# schema_esp01-chata.net
KiCad netlist of a schematic drawn in EAGLE
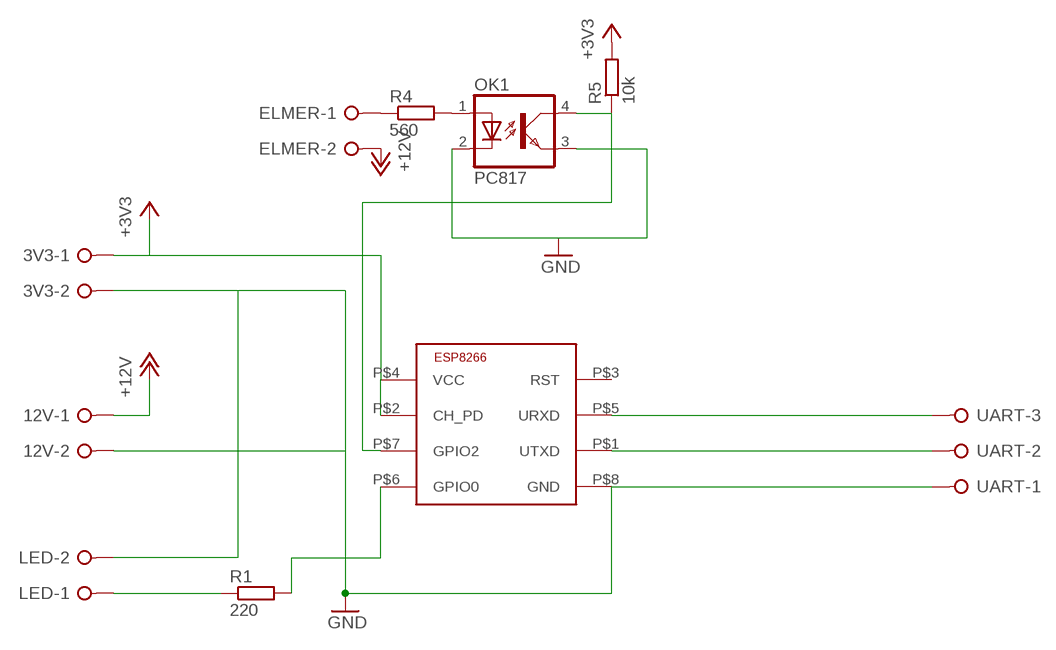
[diagram p0: schematic, sheet 1]

(export (version "E")
  (design (tool "Eeschema 10.0.6"))
  (components
    (comp (ref "3V3")
      (value "W237-02P")
      (footprint "eagle-import:W237-132")
      (libsource (lib "eagle-import") (part "W237-02P"))
    )
    (comp (ref "12V")
      (value "W237-02P")
      (footprint "eagle-import:W237-132")
      (libsource (lib "eagle-import") (part "W237-02P"))
    )
    (comp (ref "ELMER")
      (value "W237-02P")
      (footprint "eagle-import:W237-132")
      (libsource (lib "eagle-import") (part "W237-02P"))
    )
    (comp (ref "LED")
      (value "W237-02P")
      (footprint "eagle-import:W237-132")
      (libsource (lib "eagle-import") (part "W237-02P"))
    )
    (comp (ref "OK1")
      (value "PC817")
      (footprint "eagle-import:DIL04")
      (fields (field (name "MPN") "PC817X4J000F"))
      (libsource (lib "eagle-import") (part "PC817"))
    )
    (comp (ref "R1")
      (value "220")
      (footprint "eagle-import:0204_7")
      (libsource (lib "eagle-import") (part "R-EU_0204/7"))
    )
    (comp (ref "R4")
      (value "560")
      (footprint "eagle-import:0204_7")
      (libsource (lib "eagle-import") (part "R-EU_0204/7"))
    )
    (comp (ref "R5")
      (value "10k")
      (footprint "eagle-import:0204_7")
      (libsource (lib "eagle-import") (part "R-EU_0204/7"))
    )
    (comp (ref "U$1")
      (value "ESP8266-01")
      (footprint "eagle-import:ESP-01")
      (libsource (lib "eagle-import") (part "ESP8266-01"))
    )
    (comp (ref "UART")
      (value "W237-3E")
      (footprint "eagle-import:W237-3E")
      (libsource (lib "eagle-import") (part "W237-3E"))
    )
  )
  (nets
    (net (code "1") (name "+3V3") (class "Default")
      (node (ref "3V3") (pin "1") (pinfunction "KL_1") (pintype "passive"))
      (node (ref "R5") (pin "2") (pinfunction "2_2") (pintype "passive"))
      (node (ref "U$1") (pin "P$2") (pinfunction "CH_PD_P$2") (pintype "bidirectional"))
      (node (ref "U$1") (pin "P$4") (pinfunction "VCC_P$4") (pintype "bidirectional"))
    )
    (net (code "2") (name "+12V") (class "Default")
      (node (ref "12V") (pin "1") (pinfunction "KL_1") (pintype "passive"))
      (node (ref "ELMER") (pin "2") (pinfunction "KL_2") (pintype "passive"))
    )
    (net (code "3") (name "GND") (class "Default")
      (node (ref "12V") (pin "2") (pinfunction "KL_2") (pintype "passive"))
      (node (ref "3V3") (pin "2") (pinfunction "KL_2") (pintype "passive"))
      (node (ref "LED") (pin "2") (pinfunction "KL_2") (pintype "passive"))
      (node (ref "OK1") (pin "2") (pinfunction "C_2") (pintype "passive"))
      (node (ref "OK1") (pin "3") (pinfunction "EMIT_3") (pintype "passive"))
      (node (ref "U$1") (pin "P$8") (pinfunction "GND_P$8") (pintype "bidirectional"))
      (node (ref "UART") (pin "1") (pinfunction "KL_1") (pintype "passive"))
    )
    (net (code "4") (name "Net-(ELMERA-KL)") (class "Default")
      (node (ref "ELMER") (pin "1") (pinfunction "KL_1") (pintype "passive"))
      (node (ref "R4") (pin "1") (pinfunction "1_1") (pintype "passive"))
    )
    (net (code "5") (name "Net-(LEDA-KL)") (class "Default")
      (node (ref "LED") (pin "1") (pinfunction "KL_1") (pintype "passive"))
      (node (ref "R1") (pin "1") (pinfunction "1_1") (pintype "passive"))
    )
    (net (code "6") (name "Net-(OK1-A)") (class "Default")
      (node (ref "OK1") (pin "1") (pinfunction "A_1") (pintype "passive"))
      (node (ref "R4") (pin "2") (pinfunction "2_2") (pintype "passive"))
    )
    (net (code "7") (name "Net-(OK1-COL)") (class "Default")
      (node (ref "OK1") (pin "4") (pinfunction "COL_4") (pintype "passive"))
      (node (ref "R5") (pin "1") (pinfunction "1_1") (pintype "passive"))
      (node (ref "U$1") (pin "P$7") (pinfunction "GPIO2_P$7") (pintype "bidirectional"))
    )
    (net (code "8") (name "Net-(U$1-GPIO0)") (class "Default")
      (node (ref "R1") (pin "2") (pinfunction "2_2") (pintype "passive"))
      (node (ref "U$1") (pin "P$6") (pinfunction "GPIO0_P$6") (pintype "bidirectional"))
    )
    (net (code "9") (name "Net-(U$1-URXD)") (class "Default")
      (node (ref "U$1") (pin "P$5") (pinfunction "URXD_P$5") (pintype "bidirectional"))
      (node (ref "UART") (pin "3") (pinfunction "KL_3") (pintype "passive"))
    )
    (net (code "10") (name "Net-(U$1-UTXD)") (class "Default")
      (node (ref "U$1") (pin "P$1") (pinfunction "UTXD_P$1") (pintype "bidirectional"))
      (node (ref "UART") (pin "2") (pinfunction "KL_2") (pintype "passive"))
    )
    (net (code "11") (name "unconnected-(U$1-RST-PadP$3)") (class "Default")
      (node (ref "U$1") (pin "P$3") (pinfunction "RST_P$3") (pintype "bidirectional"))
    )
  )
)
